# Main.net
KiCad netlist of a schematic drawn in Altium Designer
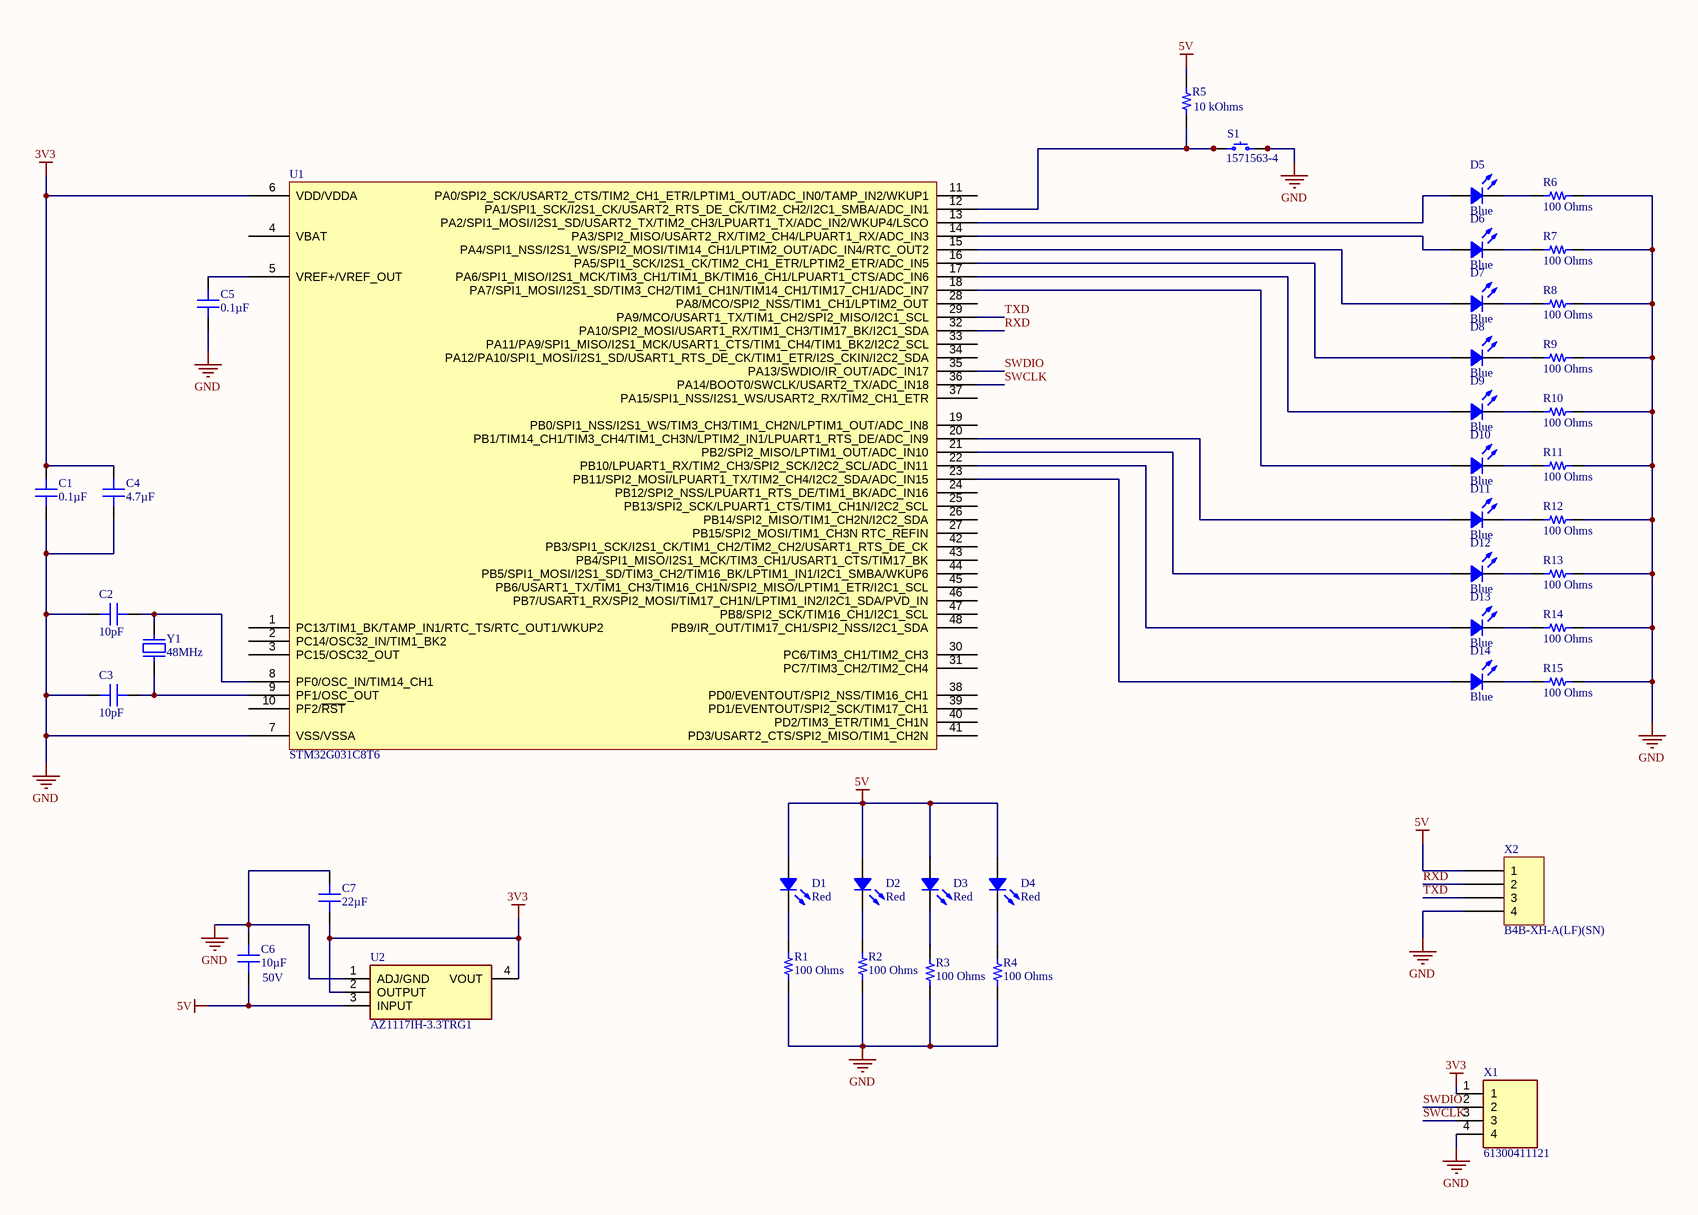
[diagram p0: Main.SchDoc]

(export (version "E")
  (design (tool "Eeschema 10.0.6"))
  (components
    (comp (ref "C1")
      (value "0.1µF")
      (footprint "CAP 0805_2012")
      (description "SMD AUTO X7R, CERAMIC, 0.1 UF, 1")
      (fields (field (name "PART NUMBER") "C0805C104K9RACAUTO") (field (name "MANUFACTURER") "KEMET"))
      (libsource (lib "Celestial Altium Library - altium_library") (part "Capacitor"))
    )
    (comp (ref "C2")
      (value "10pF")
      (footprint "CAP 0603_1608")
      (description "CAP CER 10PF 250V C0G/NP0 0603")
      (fields
        (field (name "PART NUMBER") "251R14S100JV4T")
        (field (name "MANUFACTURER") "Johanson Technology Inc.")
      )
      (libsource (lib "Celestial Altium Library - altium_library") (part "Capacitor"))
    )
    (comp (ref "C3")
      (value "10pF")
      (footprint "CAP 0603_1608")
      (description "CAP CER 10PF 250V C0G/NP0 0603")
      (fields
        (field (name "PART NUMBER") "251R14S100JV4T")
        (field (name "MANUFACTURER") "Johanson Technology Inc.")
      )
      (libsource (lib "Celestial Altium Library - altium_library") (part "Capacitor"))
    )
    (comp (ref "C4")
      (value "4.7µF")
      (footprint "CAP 0805_2012")
      (description "CAP CER 4.7UF 50V JB 0805")
      (fields
        (field (name "PART NUMBER") "C2012JB1H475K125AB")
        (field (name "MANUFACTURER") "TDK Corporation")
      )
      (libsource (lib "Celestial Altium Library - altium_library") (part "Capacitor"))
    )
    (comp (ref "C5")
      (value "0.1µF")
      (footprint "CAP 0805_2012")
      (description "SMD AUTO X7R, CERAMIC, 0.1 UF, 1")
      (fields (field (name "PART NUMBER") "C0805C104K9RACAUTO") (field (name "MANUFACTURER") "KEMET"))
      (libsource (lib "Celestial Altium Library - altium_library") (part "Capacitor"))
    )
    (comp (ref "C6")
      (value "10µF")
      (footprint "CAP 0805_2012")
      (description "0805 (2012MM) X5R (EIA) 50VDC 10")
      (fields
        (field (name "PART NUMBER") "GRM21BR61H106KE43L")
        (field (name "MANUFACTURER") "Murata Electronics")
        (field (name "VOLTAGE - RATED") "50V")
      )
      (libsource (lib "Celestial Altium Library - altium_library") (part "Capacitor"))
    )
    (comp (ref "C7")
      (value "22µF")
      (footprint "CAP 0805_2012")
      (description "CAP CER 22UF 6.3V X5R 0805")
      (fields
        (field (name "PART NUMBER") "GRM21BR60J226ME39K")
        (field (name "MANUFACTURER") "Murata Electronics")
      )
      (libsource (lib "Celestial Altium Library - altium_library") (part "Capacitor"))
    )
    (comp (ref "D1")
      (value "Red")
      (footprint "LED 1206_3216 RED")
      (description "LED RED CLEAR 1206 SMD")
      (fields (field (name "PART NUMBER") "150120RS75000") (field (name "MANUFACTURER") "Würth Elektronik"))
      (libsource (lib "Celestial Altium Library - altium_library") (part "LED"))
    )
    (comp (ref "D2")
      (value "Red")
      (footprint "LED 1206_3216 RED")
      (description "LED RED CLEAR 1206 SMD")
      (fields (field (name "PART NUMBER") "150120RS75000") (field (name "MANUFACTURER") "Würth Elektronik"))
      (libsource (lib "Celestial Altium Library - altium_library") (part "LED"))
    )
    (comp (ref "D3")
      (value "Red")
      (footprint "LED 1206_3216 RED")
      (description "LED RED CLEAR 1206 SMD")
      (fields (field (name "PART NUMBER") "150120RS75000") (field (name "MANUFACTURER") "Würth Elektronik"))
      (libsource (lib "Celestial Altium Library - altium_library") (part "LED"))
    )
    (comp (ref "D4")
      (value "Red")
      (footprint "LED 1206_3216 RED")
      (description "LED RED CLEAR 1206 SMD")
      (fields (field (name "PART NUMBER") "150120RS75000") (field (name "MANUFACTURER") "Würth Elektronik"))
      (libsource (lib "Celestial Altium Library - altium_library") (part "LED"))
    )
    (comp (ref "D5")
      (value "Blue")
      (footprint "LED 1206_3216 BLUE")
      (description "LED BLUE CLEAR 1206 SMD")
      (fields (field (name "PART NUMBER") "150120BS75000") (field (name "MANUFACTURER") "Würth Elektronik"))
      (libsource (lib "Celestial Altium Library - altium_library") (part "LED"))
    )
    (comp (ref "D6")
      (value "Blue")
      (footprint "LED 1206_3216 BLUE")
      (description "LED BLUE CLEAR 1206 SMD")
      (fields (field (name "PART NUMBER") "150120BS75000") (field (name "MANUFACTURER") "Würth Elektronik"))
      (libsource (lib "Celestial Altium Library - altium_library") (part "LED"))
    )
    (comp (ref "D7")
      (value "Blue")
      (footprint "LED 1206_3216 BLUE")
      (description "LED BLUE CLEAR 1206 SMD")
      (fields (field (name "PART NUMBER") "150120BS75000") (field (name "MANUFACTURER") "Würth Elektronik"))
      (libsource (lib "Celestial Altium Library - altium_library") (part "LED"))
    )
    (comp (ref "D8")
      (value "Blue")
      (footprint "LED 1206_3216 BLUE")
      (description "LED BLUE CLEAR 1206 SMD")
      (fields (field (name "PART NUMBER") "150120BS75000") (field (name "MANUFACTURER") "Würth Elektronik"))
      (libsource (lib "Celestial Altium Library - altium_library") (part "LED"))
    )
    (comp (ref "D9")
      (value "Blue")
      (footprint "LED 1206_3216 BLUE")
      (description "LED BLUE CLEAR 1206 SMD")
      (fields (field (name "PART NUMBER") "150120BS75000") (field (name "MANUFACTURER") "Würth Elektronik"))
      (libsource (lib "Celestial Altium Library - altium_library") (part "LED"))
    )
    (comp (ref "D10")
      (value "Blue")
      (footprint "LED 1206_3216 BLUE")
      (description "LED BLUE CLEAR 1206 SMD")
      (fields (field (name "PART NUMBER") "150120BS75000") (field (name "MANUFACTURER") "Würth Elektronik"))
      (libsource (lib "Celestial Altium Library - altium_library") (part "LED"))
    )
    (comp (ref "D11")
      (value "Blue")
      (footprint "LED 1206_3216 BLUE")
      (description "LED BLUE CLEAR 1206 SMD")
      (fields (field (name "PART NUMBER") "150120BS75000") (field (name "MANUFACTURER") "Würth Elektronik"))
      (libsource (lib "Celestial Altium Library - altium_library") (part "LED"))
    )
    (comp (ref "D12")
      (value "Blue")
      (footprint "LED 1206_3216 BLUE")
      (description "LED BLUE CLEAR 1206 SMD")
      (fields (field (name "PART NUMBER") "150120BS75000") (field (name "MANUFACTURER") "Würth Elektronik"))
      (libsource (lib "Celestial Altium Library - altium_library") (part "LED"))
    )
    (comp (ref "D13")
      (value "Blue")
      (footprint "LED 1206_3216 BLUE")
      (description "LED BLUE CLEAR 1206 SMD")
      (fields (field (name "PART NUMBER") "150120BS75000") (field (name "MANUFACTURER") "Würth Elektronik"))
      (libsource (lib "Celestial Altium Library - altium_library") (part "LED"))
    )
    (comp (ref "D14")
      (value "Blue")
      (footprint "LED 1206_3216 BLUE")
      (description "LED BLUE CLEAR 1206 SMD")
      (fields (field (name "PART NUMBER") "150120BS75000") (field (name "MANUFACTURER") "Würth Elektronik"))
      (libsource (lib "Celestial Altium Library - altium_library") (part "LED"))
    )
    (comp (ref "R1")
      (value "100 Ohms")
      (footprint "RES 0805_2012")
      (description "RES SMD 100 OHM 1% 1/8W 0805")
      (fields (field (name "PART NUMBER") "RC0805FR-07100RP") (field (name "MANUFACTURER") "Yageo"))
      (libsource (lib "Celestial Altium Library - altium_library") (part "Resistor"))
    )
    (comp (ref "R2")
      (value "100 Ohms")
      (footprint "RES 0805_2012")
      (description "RES SMD 100 OHM 1% 1/8W 0805")
      (fields (field (name "PART NUMBER") "RC0805FR-07100RP") (field (name "MANUFACTURER") "Yageo"))
      (libsource (lib "Celestial Altium Library - altium_library") (part "Resistor"))
    )
    (comp (ref "R3")
      (value "100 Ohms")
      (footprint "RES 0805_2012")
      (description "RES SMD 100 OHM 1% 1/8W 0805")
      (fields (field (name "PART NUMBER") "RC0805FR-07100RP") (field (name "MANUFACTURER") "Yageo"))
      (libsource (lib "Celestial Altium Library - altium_library") (part "Resistor"))
    )
    (comp (ref "R4")
      (value "100 Ohms")
      (footprint "RES 0805_2012")
      (description "RES SMD 100 OHM 1% 1/8W 0805")
      (fields (field (name "PART NUMBER") "RC0805FR-07100RP") (field (name "MANUFACTURER") "Yageo"))
      (libsource (lib "Celestial Altium Library - altium_library") (part "Resistor"))
    )
    (comp (ref "R5")
      (value "10 kOhms")
      (footprint "RES 0805_2012")
      (description "RES SMD 10K OHM 0.5% 1/8W 0805")
      (fields (field (name "PART NUMBER") "RT0805DRD0710KL") (field (name "MANUFACTURER") "Yageo"))
      (libsource (lib "Celestial Altium Library - altium_library") (part "Resistor"))
    )
    (comp (ref "R6")
      (value "100 Ohms")
      (footprint "RES 0805_2012")
      (description "RES SMD 100 OHM 1% 1/8W 0805")
      (fields (field (name "PART NUMBER") "RC0805FR-07100RP") (field (name "MANUFACTURER") "Yageo"))
      (libsource (lib "Celestial Altium Library - altium_library") (part "Resistor"))
    )
    (comp (ref "R7")
      (value "100 Ohms")
      (footprint "RES 0805_2012")
      (description "RES SMD 100 OHM 1% 1/8W 0805")
      (fields (field (name "PART NUMBER") "RC0805FR-07100RP") (field (name "MANUFACTURER") "Yageo"))
      (libsource (lib "Celestial Altium Library - altium_library") (part "Resistor"))
    )
    (comp (ref "R8")
      (value "100 Ohms")
      (footprint "RES 0805_2012")
      (description "RES SMD 100 OHM 1% 1/8W 0805")
      (fields (field (name "PART NUMBER") "RC0805FR-07100RP") (field (name "MANUFACTURER") "Yageo"))
      (libsource (lib "Celestial Altium Library - altium_library") (part "Resistor"))
    )
    (comp (ref "R9")
      (value "100 Ohms")
      (footprint "RES 0805_2012")
      (description "RES SMD 100 OHM 1% 1/8W 0805")
      (fields (field (name "PART NUMBER") "RC0805FR-07100RP") (field (name "MANUFACTURER") "Yageo"))
      (libsource (lib "Celestial Altium Library - altium_library") (part "Resistor"))
    )
    (comp (ref "R10")
      (value "100 Ohms")
      (footprint "RES 0805_2012")
      (description "RES SMD 100 OHM 1% 1/8W 0805")
      (fields (field (name "PART NUMBER") "RC0805FR-07100RP") (field (name "MANUFACTURER") "Yageo"))
      (libsource (lib "Celestial Altium Library - altium_library") (part "Resistor"))
    )
    (comp (ref "R11")
      (value "100 Ohms")
      (footprint "RES 0805_2012")
      (description "RES SMD 100 OHM 1% 1/8W 0805")
      (fields (field (name "PART NUMBER") "RC0805FR-07100RP") (field (name "MANUFACTURER") "Yageo"))
      (libsource (lib "Celestial Altium Library - altium_library") (part "Resistor"))
    )
    (comp (ref "R12")
      (value "100 Ohms")
      (footprint "RES 0805_2012")
      (description "RES SMD 100 OHM 1% 1/8W 0805")
      (fields (field (name "PART NUMBER") "RC0805FR-07100RP") (field (name "MANUFACTURER") "Yageo"))
      (libsource (lib "Celestial Altium Library - altium_library") (part "Resistor"))
    )
    (comp (ref "R13")
      (value "100 Ohms")
      (footprint "RES 0805_2012")
      (description "RES SMD 100 OHM 1% 1/8W 0805")
      (fields (field (name "PART NUMBER") "RC0805FR-07100RP") (field (name "MANUFACTURER") "Yageo"))
      (libsource (lib "Celestial Altium Library - altium_library") (part "Resistor"))
    )
    (comp (ref "R14")
      (value "100 Ohms")
      (footprint "RES 0805_2012")
      (description "RES SMD 100 OHM 1% 1/8W 0805")
      (fields (field (name "PART NUMBER") "RC0805FR-07100RP") (field (name "MANUFACTURER") "Yageo"))
      (libsource (lib "Celestial Altium Library - altium_library") (part "Resistor"))
    )
    (comp (ref "R15")
      (value "100 Ohms")
      (footprint "RES 0805_2012")
      (description "RES SMD 100 OHM 1% 1/8W 0805")
      (fields (field (name "PART NUMBER") "RC0805FR-07100RP") (field (name "MANUFACTURER") "Yageo"))
      (libsource (lib "Celestial Altium Library - altium_library") (part "Resistor"))
    )
    (comp (ref "S1")
      (value "1571563-4")
      (footprint "TE FSM4JSMA")
      (description "SWITCH TACTILE SPST-NO 0.05A 24V")
      (fields (field (name "MANUFACTURER") "TE Connectivity ALCOSWITCH Switches"))
      (libsource (lib "Celestial Altium Library - altium_library") (part "SPST-NO 4 PIN"))
    )
    (comp (ref "U1")
      (value "STM32G031C8T6")
      (footprint "ST LQFP-48 7X7MM")
      (description "MAINSTREAM ARM CORTEX-M0+ MCU WI")
      (fields (field (name "MANUFACTURER") "STMicroelectronics"))
      (libsource (lib "Celestial Altium Library - altium_library") (part "ST STM32G031CxT LQFP48"))
    )
    (comp (ref "U2")
      (value "AZ1117IH-3.3TRG1")
      (footprint "SamacSys:SOT230P700X180-4N")
      (description "Integrated Circuit")
      (fields (field (name "MOUSER PART NUMBER") "621-AZ1117IH-3.3TRG1"))
      (libsource (lib "*") (part "AZ1117IH-3.3TRG1"))
    )
    (comp (ref "X1")
      (value "61300411121")
      (footprint "SamacSys:HDRV4W95P0X254_1X4_1016X254X854P")
      (description "Connector")
      (fields (field (name "MOUSER PART NUMBER") "710-61300411121"))
      (libsource (lib "*") (part "61300411121"))
    )
    (comp (ref "X2")
      (value "B4B-XH-A(LF)(SN)")
      (footprint "JST XH B4B-XH-A")
      (description "CONN HEADER VERT 4POS 2.5MM")
      (fields (field (name "MANUFACTURER") "JST Sales America Inc."))
      (libsource (lib "Celestial Altium Library - altium_library") (part "4 Pin"))
    )
    (comp (ref "Y1")
      (value "48MHz")
      (footprint "NDK NX5032GA")
      (description "CRYSTAL 48.0000MHZ 8PF SMD")
      (fields
        (field (name "PART NUMBER") "NX5032GA-48.000000MHZ-LN-CD-1")
        (field (name "MANUFACTURER") "NDK America, Inc.")
      )
      (libsource (lib "Celestial Altium Library - altium_library") (part "NDK Crystal NX5032GA"))
    )
  )
  (nets
    (net (code "1") (name "/RXD") (class "Default")
      (node (ref "U1") (pin "32") (pinfunction "PA10/SPI2_MOSI/USART1_RX/TIM1_CH3/TIM17_BK/I2C1_SDA_32") (pintype "passive"))
      (node (ref "X2") (pin "2") (pinfunction "2_2") (pintype "passive"))
    )
    (net (code "2") (name "/SWCLK") (class "Default")
      (node (ref "U1") (pin "36") (pinfunction "PA14/BOOT0/SWCLK/USART2_TX/ADC_IN18_36") (pintype "passive"))
      (node (ref "X1") (pin "3") (pinfunction "3_3") (pintype "passive"))
    )
    (net (code "3") (name "/SWDIO") (class "Default")
      (node (ref "U1") (pin "35") (pinfunction "PA13/SWDIO/IR_OUT/ADC_IN17_35") (pintype "passive"))
      (node (ref "X1") (pin "2") (pinfunction "2_2") (pintype "passive"))
    )
    (net (code "4") (name "/TXD") (class "Default")
      (node (ref "U1") (pin "29") (pinfunction "PA9/MCO/USART1_TX/TIM1_CH2/SPI2_MISO/I2C1_SCL_29") (pintype "passive"))
      (node (ref "X2") (pin "3") (pinfunction "3_3") (pintype "passive"))
    )
    (net (code "5") (name "3V3") (class "Default")
      (node (ref "C1") (pin "2") (pinfunction "2_2") (pintype "passive"))
      (node (ref "C4") (pin "2") (pinfunction "2_2") (pintype "passive"))
      (node (ref "C7") (pin "1") (pinfunction "1_1") (pintype "passive"))
      (node (ref "U1") (pin "6") (pinfunction "VDD/VDDA_6") (pintype "passive"))
      (node (ref "U2") (pin "2") (pinfunction "OUTPUT_2") (pintype "passive"))
      (node (ref "U2") (pin "4") (pinfunction "VOUT_4") (pintype "passive"))
      (node (ref "X1") (pin "1") (pinfunction "1_1") (pintype "passive"))
    )
    (net (code "6") (name "5V") (class "Default")
      (node (ref "C6") (pin "2") (pinfunction "2_2") (pintype "passive"))
      (node (ref "D1") (pin "1") (pinfunction "1_1") (pintype "passive"))
      (node (ref "D2") (pin "1") (pinfunction "1_1") (pintype "passive"))
      (node (ref "D3") (pin "1") (pinfunction "1_1") (pintype "passive"))
      (node (ref "D4") (pin "1") (pinfunction "1_1") (pintype "passive"))
      (node (ref "R5") (pin "2") (pinfunction "2_2") (pintype "passive"))
      (node (ref "U2") (pin "3") (pinfunction "INPUT_3") (pintype "passive"))
      (node (ref "X2") (pin "1") (pinfunction "1_1") (pintype "passive"))
    )
    (net (code "7") (name "GND") (class "Default")
      (node (ref "C1") (pin "1") (pinfunction "1_1") (pintype "passive"))
      (node (ref "C2") (pin "1") (pinfunction "1_1") (pintype "passive"))
      (node (ref "C3") (pin "1") (pinfunction "1_1") (pintype "passive"))
      (node (ref "C4") (pin "1") (pinfunction "1_1") (pintype "passive"))
      (node (ref "C5") (pin "1") (pinfunction "1_1") (pintype "passive"))
      (node (ref "C6") (pin "1") (pinfunction "1_1") (pintype "passive"))
      (node (ref "C7") (pin "2") (pinfunction "2_2") (pintype "passive"))
      (node (ref "R1") (pin "1") (pinfunction "1_1") (pintype "passive"))
      (node (ref "R10") (pin "1") (pinfunction "1_1") (pintype "passive"))
      (node (ref "R11") (pin "1") (pinfunction "1_1") (pintype "passive"))
      (node (ref "R12") (pin "1") (pinfunction "1_1") (pintype "passive"))
      (node (ref "R13") (pin "1") (pinfunction "1_1") (pintype "passive"))
      (node (ref "R14") (pin "1") (pinfunction "1_1") (pintype "passive"))
      (node (ref "R15") (pin "1") (pinfunction "1_1") (pintype "passive"))
      (node (ref "R2") (pin "1") (pinfunction "1_1") (pintype "passive"))
      (node (ref "R3") (pin "1") (pinfunction "1_1") (pintype "passive"))
      (node (ref "R4") (pin "1") (pinfunction "1_1") (pintype "passive"))
      (node (ref "R6") (pin "1") (pinfunction "1_1") (pintype "passive"))
      (node (ref "R7") (pin "1") (pinfunction "1_1") (pintype "passive"))
      (node (ref "R8") (pin "1") (pinfunction "1_1") (pintype "passive"))
      (node (ref "R9") (pin "1") (pinfunction "1_1") (pintype "passive"))
      (node (ref "S1") (pin "3") (pinfunction "3_3") (pintype "passive"))
      (node (ref "S1") (pin "4") (pinfunction "4_4") (pintype "passive"))
      (node (ref "U1") (pin "7") (pinfunction "VSS/VSSA_7") (pintype "passive"))
      (node (ref "U2") (pin "1") (pinfunction "ADJ/GND_1") (pintype "passive"))
      (node (ref "X1") (pin "4") (pinfunction "4_4") (pintype "passive"))
      (node (ref "X2") (pin "4") (pinfunction "4_4") (pintype "passive"))
    )
    (net (code "8") (name "Net-(D1-Pad2)") (class "Default")
      (node (ref "D1") (pin "2") (pinfunction "2_2") (pintype "passive"))
      (node (ref "R1") (pin "2") (pinfunction "2_2") (pintype "passive"))
    )
    (net (code "9") (name "Net-(D2-Pad2)") (class "Default")
      (node (ref "D2") (pin "2") (pinfunction "2_2") (pintype "passive"))
      (node (ref "R2") (pin "2") (pinfunction "2_2") (pintype "passive"))
    )
    (net (code "10") (name "Net-(D3-Pad2)") (class "Default")
      (node (ref "D3") (pin "2") (pinfunction "2_2") (pintype "passive"))
      (node (ref "R3") (pin "2") (pinfunction "2_2") (pintype "passive"))
    )
    (net (code "11") (name "Net-(D4-Pad2)") (class "Default")
      (node (ref "D4") (pin "2") (pinfunction "2_2") (pintype "passive"))
      (node (ref "R4") (pin "2") (pinfunction "2_2") (pintype "passive"))
    )
    (net (code "12") (name "Net-(D5-Pad2)") (class "Default")
      (node (ref "D5") (pin "2") (pinfunction "2_2") (pintype "passive"))
      (node (ref "R6") (pin "2") (pinfunction "2_2") (pintype "passive"))
    )
    (net (code "13") (name "Net-(D6-Pad2)") (class "Default")
      (node (ref "D6") (pin "2") (pinfunction "2_2") (pintype "passive"))
      (node (ref "R7") (pin "2") (pinfunction "2_2") (pintype "passive"))
    )
    (net (code "14") (name "Net-(D7-Pad2)") (class "Default")
      (node (ref "D7") (pin "2") (pinfunction "2_2") (pintype "passive"))
      (node (ref "R8") (pin "2") (pinfunction "2_2") (pintype "passive"))
    )
    (net (code "15") (name "Net-(D8-Pad2)") (class "Default")
      (node (ref "D8") (pin "2") (pinfunction "2_2") (pintype "passive"))
      (node (ref "R9") (pin "2") (pinfunction "2_2") (pintype "passive"))
    )
    (net (code "16") (name "Net-(D9-Pad2)") (class "Default")
      (node (ref "D9") (pin "2") (pinfunction "2_2") (pintype "passive"))
      (node (ref "R10") (pin "2") (pinfunction "2_2") (pintype "passive"))
    )
    (net (code "17") (name "Net-(D10-Pad2)") (class "Default")
      (node (ref "D10") (pin "2") (pinfunction "2_2") (pintype "passive"))
      (node (ref "R11") (pin "2") (pinfunction "2_2") (pintype "passive"))
    )
    (net (code "18") (name "Net-(D11-Pad2)") (class "Default")
      (node (ref "D11") (pin "2") (pinfunction "2_2") (pintype "passive"))
      (node (ref "R12") (pin "2") (pinfunction "2_2") (pintype "passive"))
    )
    (net (code "19") (name "Net-(D12-Pad2)") (class "Default")
      (node (ref "D12") (pin "2") (pinfunction "2_2") (pintype "passive"))
      (node (ref "R13") (pin "2") (pinfunction "2_2") (pintype "passive"))
    )
    (net (code "20") (name "Net-(D13-Pad2)") (class "Default")
      (node (ref "D13") (pin "2") (pinfunction "2_2") (pintype "passive"))
      (node (ref "R14") (pin "2") (pinfunction "2_2") (pintype "passive"))
    )
    (net (code "21") (name "Net-(D14-Pad2)") (class "Default")
      (node (ref "D14") (pin "2") (pinfunction "2_2") (pintype "passive"))
      (node (ref "R15") (pin "2") (pinfunction "2_2") (pintype "passive"))
    )
    (net (code "22") (name "Net-(U1-PA1{slash}SPI1_SCK{slash}I2S1_CK{slash}USART2_RTS_DE_CK{slash}TIM2_CH2{slash}I2C1_SMBA{slash}ADC_IN1)") (class "Default")
      (node (ref "R5") (pin "1") (pinfunction "1_1") (pintype "passive"))
      (node (ref "S1") (pin "1") (pinfunction "1_1") (pintype "passive"))
      (node (ref "S1") (pin "2") (pinfunction "2_2") (pintype "passive"))
      (node (ref "U1") (pin "12") (pinfunction "PA1/SPI1_SCK/I2S1_CK/USART2_RTS_DE_CK/TIM2_CH2/I2C1_SMBA/ADC_IN1_12") (pintype "passive"))
    )
    (net (code "23") (name "Net-(U1-PA2{slash}SPI1_MOSI{slash}I2S1_SD{slash}USART2_TX{slash}TIM2_CH3{slash}LPUART1_TX{slash}ADC_IN2{slash}WKUP4{slash}LSCO)") (class "Default")
      (node (ref "D5") (pin "1") (pinfunction "1_1") (pintype "passive"))
      (node (ref "U1") (pin "13") (pinfunction "PA2/SPI1_MOSI/I2S1_SD/USART2_TX/TIM2_CH3/LPUART1_TX/ADC_IN2/WKUP4/LSCO_13") (pintype "passive"))
    )
    (net (code "24") (name "Net-(U1-PA3{slash}SPI2_MISO{slash}USART2_RX{slash}TIM2_CH4{slash}LPUART1_RX{slash}ADC_IN3)") (class "Default")
      (node (ref "D6") (pin "1") (pinfunction "1_1") (pintype "passive"))
      (node (ref "U1") (pin "14") (pinfunction "PA3/SPI2_MISO/USART2_RX/TIM2_CH4/LPUART1_RX/ADC_IN3_14") (pintype "passive"))
    )
    (net (code "25") (name "Net-(U1-PA4{slash}SPI1_NSS{slash}I2S1_WS{slash}SPI2_MOSI{slash}TIM14_CH1{slash}LPTIM2_OUT{slash}ADC_IN4{slash}RTC_OUT2)") (class "Default")
      (node (ref "D7") (pin "1") (pinfunction "1_1") (pintype "passive"))
      (node (ref "U1") (pin "15") (pinfunction "PA4/SPI1_NSS/I2S1_WS/SPI2_MOSI/TIM14_CH1/LPTIM2_OUT/ADC_IN4/RTC_OUT2_15") (pintype "passive"))
    )
    (net (code "26") (name "Net-(U1-PA5{slash}SPI1_SCK{slash}I2S1_CK{slash}TIM2_CH1_ETR{slash}LPTIM2_ETR{slash}ADC_IN5)") (class "Default")
      (node (ref "D8") (pin "1") (pinfunction "1_1") (pintype "passive"))
      (node (ref "U1") (pin "16") (pinfunction "PA5/SPI1_SCK/I2S1_CK/TIM2_CH1_ETR/LPTIM2_ETR/ADC_IN5_16") (pintype "passive"))
    )
    (net (code "27") (name "Net-(U1-PA6{slash}SPI1_MISO{slash}I2S1_MCK{slash}TIM3_CH1{slash}TIM1_BK{slash}TIM16_CH1{slash}LPUART1_CTS{slash}ADC_IN6)") (class "Default")
      (node (ref "D9") (pin "1") (pinfunction "1_1") (pintype "passive"))
      (node (ref "U1") (pin "17") (pinfunction "PA6/SPI1_MISO/I2S1_MCK/TIM3_CH1/TIM1_BK/TIM16_CH1/LPUART1_CTS/ADC_IN6_17") (pintype "passive"))
    )
    (net (code "28") (name "Net-(U1-PA7{slash}SPI1_MOSI{slash}I2S1_SD{slash}TIM3_CH2{slash}TIM1_CH1N{slash}TIM14_CH1{slash}TIM17_CH1{slash}ADC_IN7)") (class "Default")
      (node (ref "D10") (pin "1") (pinfunction "1_1") (pintype "passive"))
      (node (ref "U1") (pin "18") (pinfunction "PA7/SPI1_MOSI/I2S1_SD/TIM3_CH2/TIM1_CH1N/TIM14_CH1/TIM17_CH1/ADC_IN7_18") (pintype "passive"))
    )
    (net (code "29") (name "Net-(U1-PB1{slash}TIM14_CH1{slash}TIM3_CH4{slash}TIM1_CH3N{slash}LPTIM2_IN1{slash}LPUART1_RTS_DE{slash}ADC_IN9)") (class "Default")
      (node (ref "D11") (pin "1") (pinfunction "1_1") (pintype "passive"))
      (node (ref "U1") (pin "20") (pinfunction "PB1/TIM14_CH1/TIM3_CH4/TIM1_CH3N/LPTIM2_IN1/LPUART1_RTS_DE/ADC_IN9_20") (pintype "passive"))
    )
    (net (code "30") (name "Net-(U1-PB2{slash}SPI2_MISO{slash}LPTIM1_OUT{slash}ADC_IN10)") (class "Default")
      (node (ref "D12") (pin "1") (pinfunction "1_1") (pintype "passive"))
      (node (ref "U1") (pin "21") (pinfunction "PB2/SPI2_MISO/LPTIM1_OUT/ADC_IN10_21") (pintype "passive"))
    )
    (net (code "31") (name "Net-(U1-PB10{slash}LPUART1_RX{slash}TIM2_CH3{slash}SPI2_SCK{slash}I2C2_SCL{slash}ADC_IN11)") (class "Default")
      (node (ref "D13") (pin "1") (pinfunction "1_1") (pintype "passive"))
      (node (ref "U1") (pin "22") (pinfunction "PB10/LPUART1_RX/TIM2_CH3/SPI2_SCK/I2C2_SCL/ADC_IN11_22") (pintype "passive"))
    )
    (net (code "32") (name "Net-(U1-PB11{slash}SPI2_MOSI{slash}LPUART1_TX{slash}TIM2_CH4{slash}I2C2_SDA{slash}ADC_IN15)") (class "Default")
      (node (ref "D14") (pin "1") (pinfunction "1_1") (pintype "passive"))
      (node (ref "U1") (pin "23") (pinfunction "PB11/SPI2_MOSI/LPUART1_TX/TIM2_CH4/I2C2_SDA/ADC_IN15_23") (pintype "passive"))
    )
    (net (code "33") (name "Net-(U1-PF0{slash}OSC_IN{slash}TIM14_CH1)") (class "Default")
      (node (ref "C2") (pin "2") (pinfunction "2_2") (pintype "passive"))
      (node (ref "U1") (pin "8") (pinfunction "PF0/OSC_IN/TIM14_CH1_8") (pintype "passive"))
      (node (ref "Y1") (pin "2") (pinfunction "2_2") (pintype "passive"))
    )
    (net (code "34") (name "Net-(U1-PF1{slash}OSC_OUT)") (class "Default")
      (node (ref "C3") (pin "2") (pinfunction "2_2") (pintype "passive"))
      (node (ref "U1") (pin "9") (pinfunction "PF1/OSC_OUT_9") (pintype "passive"))
      (node (ref "Y1") (pin "1") (pinfunction "1_1") (pintype "passive"))
    )
    (net (code "35") (name "Net-(U1-VREF+{slash}VREF_OUT)") (class "Default")
      (node (ref "C5") (pin "2") (pinfunction "2_2") (pintype "passive"))
      (node (ref "U1") (pin "5") (pinfunction "VREF+/VREF_OUT_5") (pintype "passive"))
    )
    (net (code "36") (name "unconnected-(U1-PA0{slash}SPI2_SCK{slash}USART2_CTS{slash}TIM2_CH1_ETR{slash}LPTIM1_OUT{slash}ADC_IN0{slash}TAMP_IN2{slash}WKUP1-Pad11)") (class "Default")
      (node (ref "U1") (pin "11") (pinfunction "PA0/SPI2_SCK/USART2_CTS/TIM2_CH1_ETR/LPTIM1_OUT/ADC_IN0/TAMP_IN2/WKUP1_11") (pintype "passive"))
    )
    (net (code "37") (name "unconnected-(U1-PA8{slash}MCO{slash}SPI2_NSS{slash}TIM1_CH1{slash}LPTIM2_OUT-Pad28)") (class "Default")
      (node (ref "U1") (pin "28") (pinfunction "PA8/MCO/SPI2_NSS/TIM1_CH1/LPTIM2_OUT_28") (pintype "passive"))
    )
    (net (code "38") (name "unconnected-(U1-PA11{slash}PA9{slash}SPI1_MISO{slash}I2S1_MCK{slash}USART1_CTS{slash}TIM1_CH4{slash}TIM1_BK2{slash}I2C2_SCL-Pad33)") (class "Default")
      (node (ref "U1") (pin "33") (pinfunction "PA11/PA9/SPI1_MISO/I2S1_MCK/USART1_CTS/TIM1_CH4/TIM1_BK2/I2C2_SCL_33") (pintype "passive"))
    )
    (net (code "39") (name "unconnected-(U1-PA12{slash}PA10{slash}SPI1_MOSI{slash}I2S1_SD{slash}USART1_RTS_DE_CK{slash}TIM1_ETR{slash}I2S_CKIN{slash}I2C2_SDA-Pad34)") (class "Default")
      (node (ref "U1") (pin "34") (pinfunction "PA12/PA10/SPI1_MOSI/I2S1_SD/USART1_RTS_DE_CK/TIM1_ETR/I2S_CKIN/I2C2_SDA_34") (pintype "passive"))
    )
    (net (code "40") (name "unconnected-(U1-PA15{slash}SPI1_NSS{slash}I2S1_WS{slash}USART2_RX{slash}TIM2_CH1_ETR-Pad37)") (class "Default")
      (node (ref "U1") (pin "37") (pinfunction "PA15/SPI1_NSS/I2S1_WS/USART2_RX/TIM2_CH1_ETR_37") (pintype "passive"))
    )
    (net (code "41") (name "unconnected-(U1-PB0{slash}SPI1_NSS{slash}I2S1_WS{slash}TIM3_CH3{slash}TIM1_CH2N{slash}LPTIM1_OUT{slash}ADC_IN8-Pad19)") (class "Default")
      (node (ref "U1") (pin "19") (pinfunction "PB0/SPI1_NSS/I2S1_WS/TIM3_CH3/TIM1_CH2N/LPTIM1_OUT/ADC_IN8_19") (pintype "passive"))
    )
    (net (code "42") (name "unconnected-(U1-PB3{slash}SPI1_SCK{slash}I2S1_CK{slash}TIM1_CH2{slash}TIM2_CH2{slash}USART1_RTS_DE_CK-Pad42)") (class "Default")
      (node (ref "U1") (pin "42") (pinfunction "PB3/SPI1_SCK/I2S1_CK/TIM1_CH2/TIM2_CH2/USART1_RTS_DE_CK_42") (pintype "passive"))
    )
    (net (code "43") (name "unconnected-(U1-PB4{slash}SPI1_MISO{slash}I2S1_MCK{slash}TIM3_CH1{slash}USART1_CTS{slash}TIM17_BK-Pad43)") (class "Default")
      (node (ref "U1") (pin "43") (pinfunction "PB4/SPI1_MISO/I2S1_MCK/TIM3_CH1/USART1_CTS/TIM17_BK_43") (pintype "passive"))
    )
    (net (code "44") (name "unconnected-(U1-PB5{slash}SPI1_MOSI{slash}I2S1_SD{slash}TIM3_CH2{slash}TIM16_BK{slash}LPTIM1_IN1{slash}I2C1_SMBA{slash}WKUP6-Pad44)") (class "Default")
      (node (ref "U1") (pin "44") (pinfunction "PB5/SPI1_MOSI/I2S1_SD/TIM3_CH2/TIM16_BK/LPTIM1_IN1/I2C1_SMBA/WKUP6_44") (pintype "passive"))
    )
    (net (code "45") (name "unconnected-(U1-PB6{slash}USART1_TX{slash}TIM1_CH3{slash}TIM16_CH1N{slash}SPI2_MISO{slash}LPTIM1_ETR{slash}I2C1_SCL-Pad45)") (class "Default")
      (node (ref "U1") (pin "45") (pinfunction "PB6/USART1_TX/TIM1_CH3/TIM16_CH1N/SPI2_MISO/LPTIM1_ETR/I2C1_SCL_45") (pintype "passive"))
    )
    (net (code "46") (name "unconnected-(U1-PB7{slash}USART1_RX{slash}SPI2_MOSI{slash}TIM17_CH1N{slash}LPTIM1_IN2{slash}I2C1_SDA{slash}PVD_IN-Pad46)") (class "Default")
      (node (ref "U1") (pin "46") (pinfunction "PB7/USART1_RX/SPI2_MOSI/TIM17_CH1N/LPTIM1_IN2/I2C1_SDA/PVD_IN_46") (pintype "passive"))
    )
    (net (code "47") (name "unconnected-(U1-PB8{slash}SPI2_SCK{slash}TIM16_CH1{slash}I2C1_SCL-Pad47)") (class "Default")
      (node (ref "U1") (pin "47") (pinfunction "PB8/SPI2_SCK/TIM16_CH1/I2C1_SCL_47") (pintype "passive"))
    )
    (net (code "48") (name "unconnected-(U1-PB9{slash}IR_OUT{slash}TIM17_CH1{slash}SPI2_NSS{slash}I2C1_SDA-Pad48)") (class "Default")
      (node (ref "U1") (pin "48") (pinfunction "PB9/IR_OUT/TIM17_CH1/SPI2_NSS/I2C1_SDA_48") (pintype "passive"))
    )
    (net (code "49") (name "unconnected-(U1-PB12{slash}SPI2_NSS{slash}LPUART1_RTS_DE{slash}TIM1_BK{slash}ADC_IN16-Pad24)") (class "Default")
      (node (ref "U1") (pin "24") (pinfunction "PB12/SPI2_NSS/LPUART1_RTS_DE/TIM1_BK/ADC_IN16_24") (pintype "passive"))
    )
    (net (code "50") (name "unconnected-(U1-PB13{slash}SPI2_SCK{slash}LPUART1_CTS{slash}TIM1_CH1N{slash}I2C2_SCL-Pad25)") (class "Default")
      (node (ref "U1") (pin "25") (pinfunction "PB13/SPI2_SCK/LPUART1_CTS/TIM1_CH1N/I2C2_SCL_25") (pintype "passive"))
    )
    (net (code "51") (name "unconnected-(U1-PB14{slash}SPI2_MISO{slash}TIM1_CH2N{slash}I2C2_SDA-Pad26)") (class "Default")
      (node (ref "U1") (pin "26") (pinfunction "PB14/SPI2_MISO/TIM1_CH2N/I2C2_SDA_26") (pintype "passive"))
    )
    (net (code "52") (name "unconnected-(U1-PB15{slash}SPI2_MOSI{slash}TIM1_CH3N_RTC_REFIN-Pad27)") (class "Default")
      (node (ref "U1") (pin "27") (pinfunction "PB15/SPI2_MOSI/TIM1_CH3N_RTC_REFIN_27") (pintype "passive"))
    )
    (net (code "53") (name "unconnected-(U1-PC6{slash}TIM3_CH1{slash}TIM2_CH3-Pad30)") (class "Default")
      (node (ref "U1") (pin "30") (pinfunction "PC6/TIM3_CH1/TIM2_CH3_30") (pintype "passive"))
    )
    (net (code "54") (name "unconnected-(U1-PC7{slash}TIM3_CH2{slash}TIM2_CH4-Pad31)") (class "Default")
      (node (ref "U1") (pin "31") (pinfunction "PC7/TIM3_CH2/TIM2_CH4_31") (pintype "passive"))
    )
    (net (code "55") (name "unconnected-(U1-PC13{slash}TIM1_BK{slash}TAMP_IN1{slash}RTC_TS{slash}RTC_OUT1{slash}WKUP2-Pad1)") (class "Default")
      (node (ref "U1") (pin "1") (pinfunction "PC13/TIM1_BK/TAMP_IN1/RTC_TS/RTC_OUT1/WKUP2_1") (pintype "passive"))
    )
    (net (code "56") (name "unconnected-(U1-PC14{slash}OSC32_IN{slash}TIM1_BK2-Pad2)") (class "Default")
      (node (ref "U1") (pin "2") (pinfunction "PC14/OSC32_IN/TIM1_BK2_2") (pintype "passive"))
    )
    (net (code "57") (name "unconnected-(U1-PC15{slash}OSC32_OUT-Pad3)") (class "Default")
      (node (ref "U1") (pin "3") (pinfunction "PC15/OSC32_OUT_3") (pintype "passive"))
    )
    (net (code "58") (name "unconnected-(U1-PD0{slash}EVENTOUT{slash}SPI2_NSS{slash}TIM16_CH1-Pad38)") (class "Default")
      (node (ref "U1") (pin "38") (pinfunction "PD0/EVENTOUT/SPI2_NSS/TIM16_CH1_38") (pintype "passive"))
    )
    (net (code "59") (name "unconnected-(U1-PD1{slash}EVENTOUT{slash}SPI2_SCK{slash}TIM17_CH1-Pad39)") (class "Default")
      (node (ref "U1") (pin "39") (pinfunction "PD1/EVENTOUT/SPI2_SCK/TIM17_CH1_39") (pintype "passive"))
    )
    (net (code "60") (name "unconnected-(U1-PD2{slash}TIM3_ETR{slash}TIM1_CH1N-Pad40)") (class "Default")
      (node (ref "U1") (pin "40") (pinfunction "PD2/TIM3_ETR/TIM1_CH1N_40") (pintype "passive"))
    )
    (net (code "61") (name "unconnected-(U1-PD3{slash}USART2_CTS{slash}SPI2_MISO{slash}TIM1_CH2N-Pad41)") (class "Default")
      (node (ref "U1") (pin "41") (pinfunction "PD3/USART2_CTS/SPI2_MISO/TIM1_CH2N_41") (pintype "passive"))
    )
    (net (code "62") (name "unconnected-(U1-PF2{slash}~{RST}-Pad10)") (class "Default")
      (node (ref "U1") (pin "10") (pinfunction "PF2/~{RST}_10") (pintype "passive"))
    )
    (net (code "63") (name "unconnected-(U1-VBAT-Pad4)") (class "Default")
      (node (ref "U1") (pin "4") (pinfunction "VBAT_4") (pintype "passive"))
    )
  )
)
